# MotorDriver.net
KiCad netlist of a schematic drawn in Altium Designer
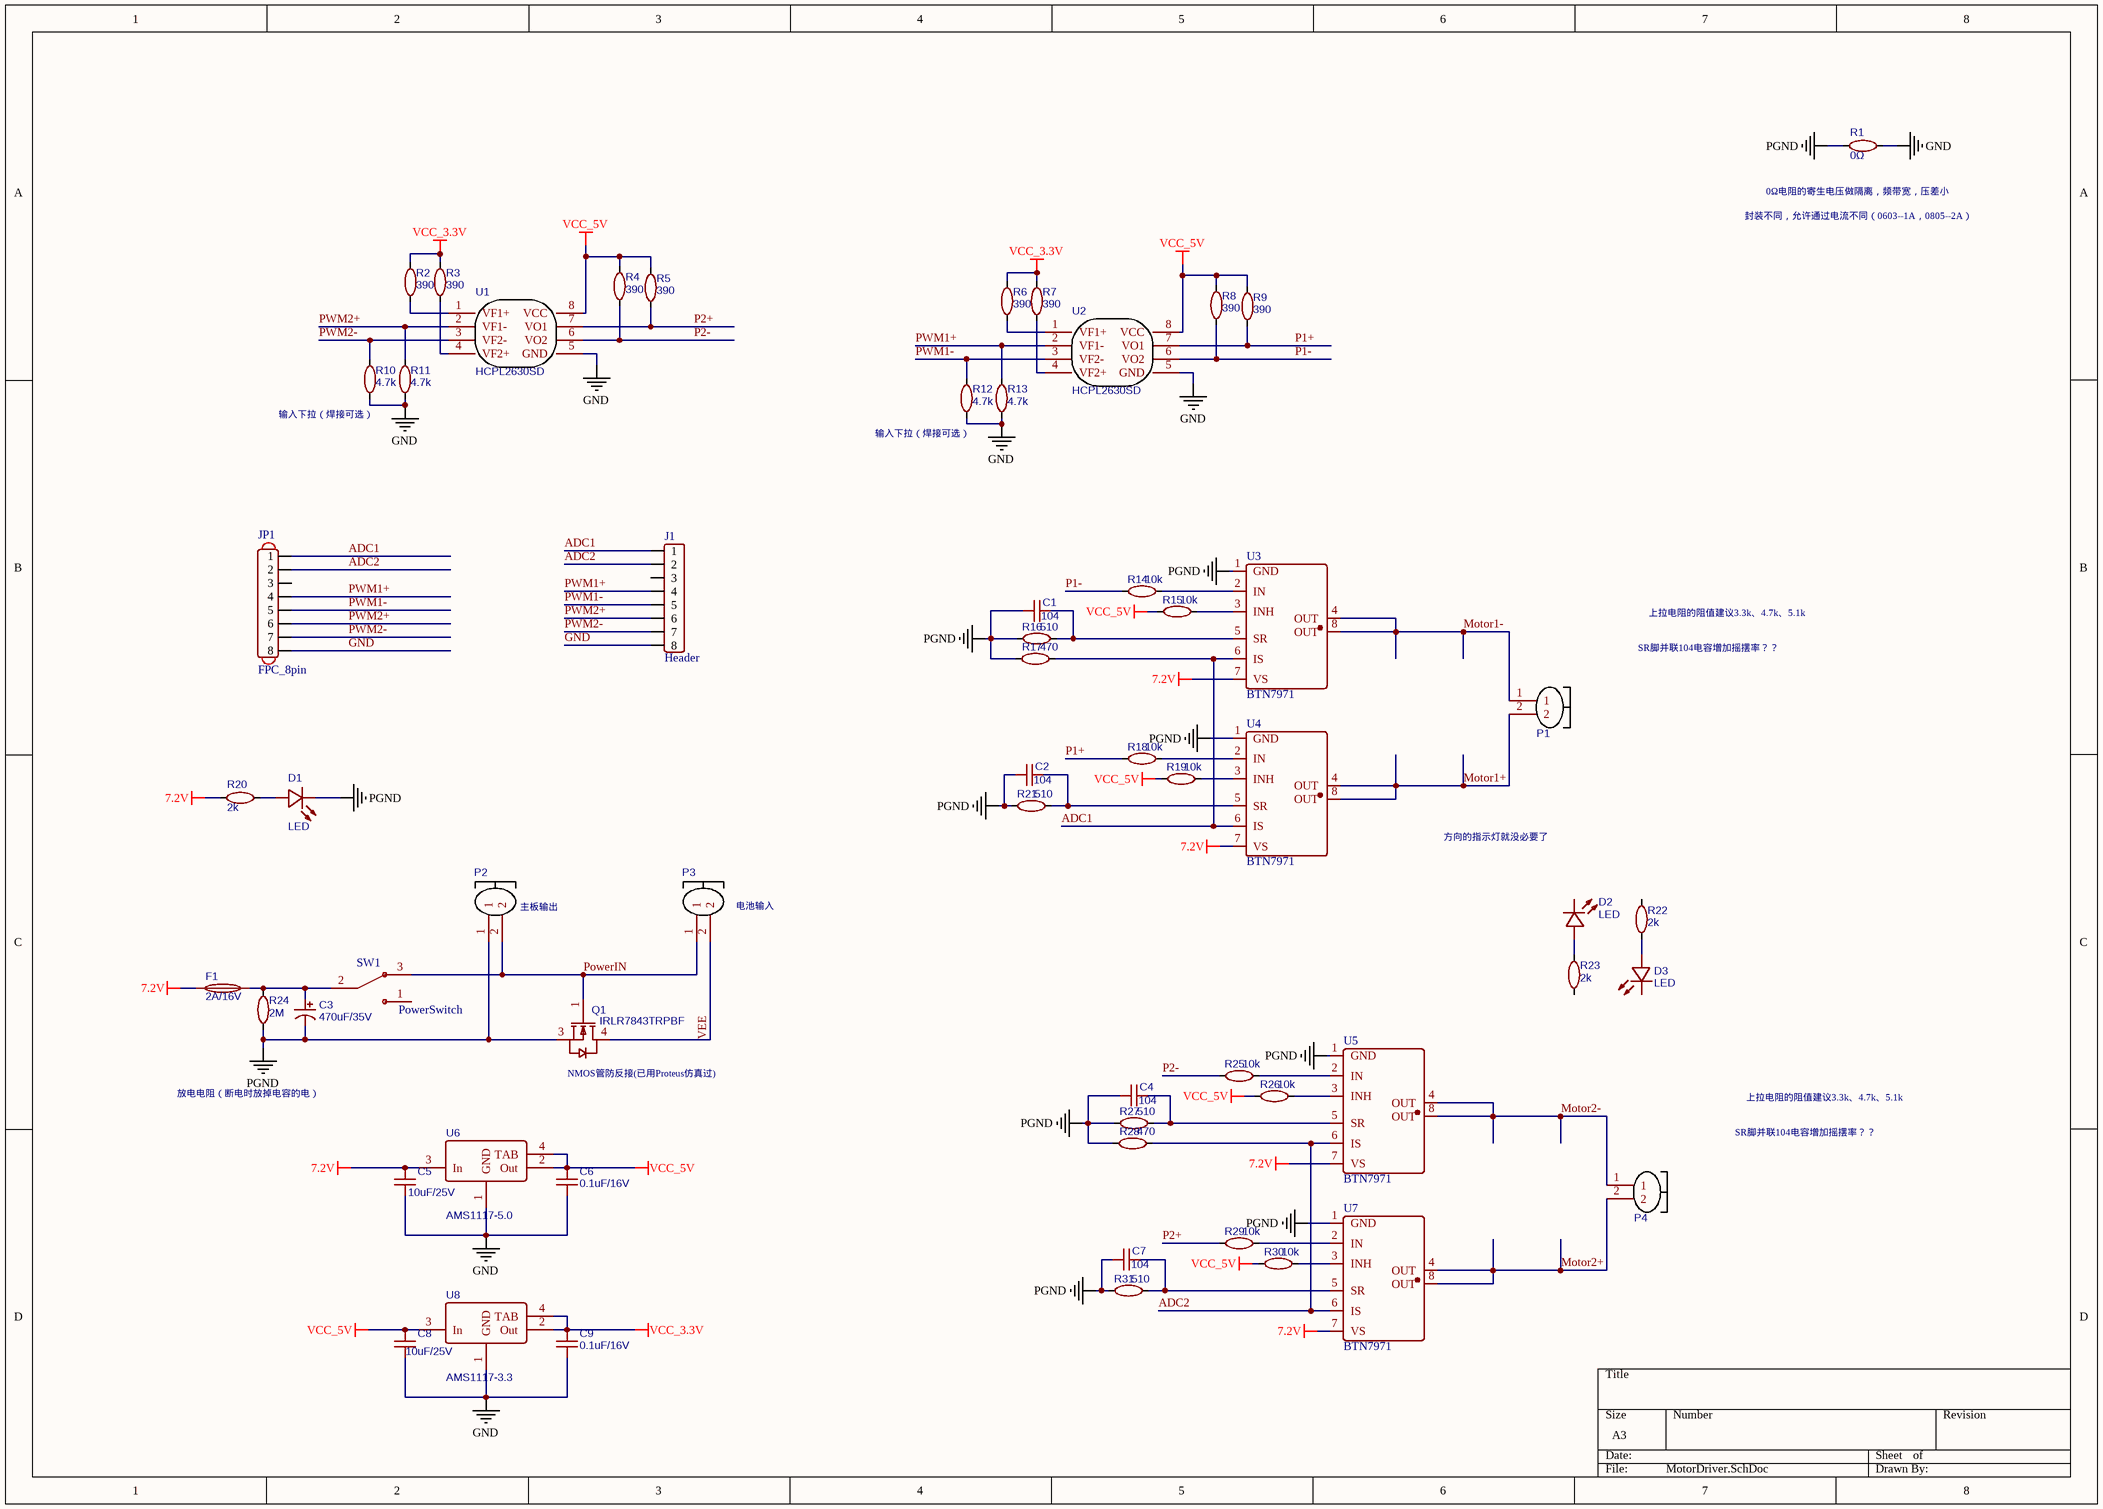
[diagram p0: MotorDriver.SchDoc]

(export (version "E")
  (design (tool "Eeschema 10.0.6"))
  (components
    (comp (ref "C1")
      (value "104")
      (footprint "CAP_0603")
      (fields
        (field (name "BOM_SUPPLIER PART") "C307348")
        (field (name "BOM_MANUFACTURER PART") "CL10B104KB8WPNC")
        (field (name "CONTRIBUTOR") "LCSC")
      )
      (libsource (lib "LTC_Library1") (part "CAP_0603"))
    )
    (comp (ref "C2")
      (value "104")
      (footprint "CAP_0603")
      (fields
        (field (name "BOM_SUPPLIER PART") "C307348")
        (field (name "BOM_MANUFACTURER PART") "CL10B104KB8WPNC")
        (field (name "CONTRIBUTOR") "LCSC")
      )
      (libsource (lib "LTC_Library1") (part "CAP_0603"))
    )
    (comp (ref "C3")
      (value "470uF/35V")
      (footprint "CAPE_TH_3.5_8")
      (description "直插电解电容")
      (fields
        (field (name "BOM_MANUFACTURER PART") "RVT1C221M0607")
        (field (name "BOM_SUPPLIER PART") "C72496")
      )
      (libsource (lib "LTC_Library1") (part "CAP_E_DIP"))
    )
    (comp (ref "C4")
      (value "104")
      (footprint "CAP_0603")
      (fields
        (field (name "BOM_SUPPLIER PART") "C307348")
        (field (name "BOM_MANUFACTURER PART") "CL10B104KB8WPNC")
        (field (name "CONTRIBUTOR") "LCSC")
      )
      (libsource (lib "LTC_Library1") (part "CAP_0603"))
    )
    (comp (ref "C5")
      (value "10uF/25V")
      (footprint "CAP_0603")
      (fields
        (field (name "BOM_SUPPLIER PART") "C307348")
        (field (name "BOM_MANUFACTURER PART") "CL10B104KB8WPNC")
        (field (name "CONTRIBUTOR") "LCSC")
      )
      (libsource (lib "LTC_Library1") (part "CAP_0603"))
    )
    (comp (ref "C6")
      (value "0.1uF/16V")
      (footprint "CAP_0603")
      (fields
        (field (name "BOM_SUPPLIER PART") "C307348")
        (field (name "BOM_MANUFACTURER PART") "CL10B104KB8WPNC")
        (field (name "CONTRIBUTOR") "LCSC")
      )
      (libsource (lib "LTC_Library1") (part "CAP_0603"))
    )
    (comp (ref "C7")
      (value "104")
      (footprint "CAP_0603")
      (fields
        (field (name "BOM_SUPPLIER PART") "C307348")
        (field (name "BOM_MANUFACTURER PART") "CL10B104KB8WPNC")
        (field (name "CONTRIBUTOR") "LCSC")
      )
      (libsource (lib "LTC_Library1") (part "CAP_0603"))
    )
    (comp (ref "C8")
      (value "10uF/25V")
      (footprint "CAP_0603")
      (fields
        (field (name "BOM_SUPPLIER PART") "C307348")
        (field (name "BOM_MANUFACTURER PART") "CL10B104KB8WPNC")
        (field (name "CONTRIBUTOR") "LCSC")
      )
      (libsource (lib "LTC_Library1") (part "CAP_0603"))
    )
    (comp (ref "C9")
      (value "0.1uF/16V")
      (footprint "CAP_0603")
      (fields
        (field (name "BOM_SUPPLIER PART") "C307348")
        (field (name "BOM_MANUFACTURER PART") "CL10B104KB8WPNC")
        (field (name "CONTRIBUTOR") "LCSC")
      )
      (libsource (lib "LTC_Library1") (part "CAP_0603"))
    )
    (comp (ref "D1")
      (value "LED")
      (footprint "LED_0603_B")
      (description "发光LED")
      (fields
        (field (name "BOM_MANUFACTURER PART") "D-G080508G1")
        (field (name "BOM_SUPPLIER PART") "C107402")
        (field (name "CONTRIBUTOR") "LCSC")
      )
      (libsource (lib "LTC_Library1") (part "LED_0603"))
    )
    (comp (ref "D2")
      (value "LED")
      (footprint "LED_0603_B")
      (description "发光LED")
      (fields
        (field (name "BOM_MANUFACTURER PART") "D-G080508G1")
        (field (name "BOM_SUPPLIER PART") "C107402")
        (field (name "CONTRIBUTOR") "LCSC")
      )
      (libsource (lib "LTC_Library1") (part "LED_0603"))
    )
    (comp (ref "D3")
      (value "LED")
      (footprint "LED_0603_B")
      (description "发光LED")
      (fields
        (field (name "BOM_MANUFACTURER PART") "D-G080508G1")
        (field (name "BOM_SUPPLIER PART") "C107402")
        (field (name "CONTRIBUTOR") "LCSC")
      )
      (libsource (lib "LTC_Library1") (part "LED_0603"))
    )
    (comp (ref "F1")
      (value "2A/16V")
      (footprint "F1206")
      (fields
        (field (name "BOM_SUPPLIER PART") "C369161")
        (field (name "BOM_MANUFACTURER PART") "JK-NSMD100-16V")
        (field (name "CONTRIBUTOR") "LCSC")
      )
      (libsource (lib "SmartCar_Library") (part "JK-NSMD100-16V"))
    )
    (comp (ref "J1")
      (value "Header")
      (footprint "Header 2.54X8")
      (libsource (lib "LTC_Library1") (part "Header 2.54_8"))
    )
    (comp (ref "JP1")
      (value "FPC_8pin")
      (footprint "FPC_1.0_8P")
      (libsource (lib "LTC_Library1") (part "FPC_8pin"))
    )
    (comp (ref "P1")
      (value "KF-2P-5.08")
      (footprint "KF_2P-5.08")
      (description "端子2P")
      (fields
        (field (name "BOM_MANUFACTURER PART") "WJ500H-5.08-2P")
        (field (name "BOM_SUPPLIER PART") "C8478")
      )
      (libsource (lib "LTC_Library1") (part "KF-2P-5.08"))
    )
    (comp (ref "P2")
      (value "KF-2P-5.08")
      (footprint "KF_2P-5.08")
      (description "端子2P")
      (fields
        (field (name "BOM_MANUFACTURER PART") "WJ500H-5.08-2P")
        (field (name "BOM_SUPPLIER PART") "C8478")
      )
      (libsource (lib "LTC_Library1") (part "KF-2P-5.08"))
    )
    (comp (ref "P3")
      (value "KF-2P-5.08")
      (footprint "KF_2P-5.08")
      (description "端子2P")
      (fields
        (field (name "BOM_MANUFACTURER PART") "WJ500H-5.08-2P")
        (field (name "BOM_SUPPLIER PART") "C8478")
      )
      (libsource (lib "LTC_Library1") (part "KF-2P-5.08"))
    )
    (comp (ref "P4")
      (value "KF-2P-5.08")
      (footprint "KF_2P-5.08")
      (description "端子2P")
      (fields
        (field (name "BOM_MANUFACTURER PART") "WJ500H-5.08-2P")
        (field (name "BOM_SUPPLIER PART") "C8478")
      )
      (libsource (lib "LTC_Library1") (part "KF-2P-5.08"))
    )
    (comp (ref "Q1")
      (value "IRLR7843TRPBF")
      (footprint "TO-252-2")
      (description "MOS管")
      (fields (field (name "BOM_SUPPLIER PART") "C21988"))
      (libsource (lib "LTC_Library1") (part "IRLR7843TRPBF"))
    )
    (comp (ref "R1")
      (value "0Ω")
      (footprint "RES_0805")
      (fields
        (field (name "BOM_MANUFACTURER PART") "RC0402JR-07100KL")
        (field (name "BOM_SUPPLIER PART") "C106234")
      )
      (libsource (lib "LTC_Library1") (part "RES_0805"))
    )
    (comp (ref "R2")
      (value "390")
      (footprint "RES_0603")
      (fields
        (field (name "BOM_MANUFACTURER PART") "RC0402JR-07100KL")
        (field (name "BOM_SUPPLIER PART") "C106234")
      )
      (libsource (lib "LTC_Library1") (part "RES_0603"))
    )
    (comp (ref "R3")
      (value "390")
      (footprint "RES_0603")
      (fields
        (field (name "BOM_MANUFACTURER PART") "RC0402JR-07100KL")
        (field (name "BOM_SUPPLIER PART") "C106234")
      )
      (libsource (lib "LTC_Library1") (part "RES_0603"))
    )
    (comp (ref "R4")
      (value "390")
      (footprint "RES_0603")
      (fields
        (field (name "BOM_MANUFACTURER PART") "RC0402JR-07100KL")
        (field (name "BOM_SUPPLIER PART") "C106234")
      )
      (libsource (lib "LTC_Library1") (part "RES_0603"))
    )
    (comp (ref "R5")
      (value "390")
      (footprint "RES_0603")
      (fields
        (field (name "BOM_MANUFACTURER PART") "RC0402JR-07100KL")
        (field (name "BOM_SUPPLIER PART") "C106234")
      )
      (libsource (lib "LTC_Library1") (part "RES_0603"))
    )
    (comp (ref "R6")
      (value "390")
      (footprint "RES_0603")
      (fields
        (field (name "BOM_MANUFACTURER PART") "RC0402JR-07100KL")
        (field (name "BOM_SUPPLIER PART") "C106234")
      )
      (libsource (lib "LTC_Library1") (part "RES_0603"))
    )
    (comp (ref "R7")
      (value "390")
      (footprint "RES_0603")
      (fields
        (field (name "BOM_MANUFACTURER PART") "RC0402JR-07100KL")
        (field (name "BOM_SUPPLIER PART") "C106234")
      )
      (libsource (lib "LTC_Library1") (part "RES_0603"))
    )
    (comp (ref "R8")
      (value "390")
      (footprint "RES_0603")
      (fields
        (field (name "BOM_MANUFACTURER PART") "RC0402JR-07100KL")
        (field (name "BOM_SUPPLIER PART") "C106234")
      )
      (libsource (lib "LTC_Library1") (part "RES_0603"))
    )
    (comp (ref "R9")
      (value "390")
      (footprint "RES_0603")
      (fields
        (field (name "BOM_MANUFACTURER PART") "RC0402JR-07100KL")
        (field (name "BOM_SUPPLIER PART") "C106234")
      )
      (libsource (lib "LTC_Library1") (part "RES_0603"))
    )
    (comp (ref "R10")
      (value "4.7k")
      (footprint "RES_0603")
      (fields
        (field (name "BOM_MANUFACTURER PART") "RC0402JR-07100KL")
        (field (name "BOM_SUPPLIER PART") "C106234")
      )
      (libsource (lib "LTC_Library1") (part "RES_0603"))
    )
    (comp (ref "R11")
      (value "4.7k")
      (footprint "RES_0603")
      (fields
        (field (name "BOM_MANUFACTURER PART") "RC0402JR-07100KL")
        (field (name "BOM_SUPPLIER PART") "C106234")
      )
      (libsource (lib "LTC_Library1") (part "RES_0603"))
    )
    (comp (ref "R12")
      (value "4.7k")
      (footprint "RES_0603")
      (fields
        (field (name "BOM_MANUFACTURER PART") "RC0402JR-07100KL")
        (field (name "BOM_SUPPLIER PART") "C106234")
      )
      (libsource (lib "LTC_Library1") (part "RES_0603"))
    )
    (comp (ref "R13")
      (value "4.7k")
      (footprint "RES_0603")
      (fields
        (field (name "BOM_MANUFACTURER PART") "RC0402JR-07100KL")
        (field (name "BOM_SUPPLIER PART") "C106234")
      )
      (libsource (lib "LTC_Library1") (part "RES_0603"))
    )
    (comp (ref "R14")
      (value "10k")
      (footprint "RES_0603")
      (fields
        (field (name "BOM_MANUFACTURER PART") "RC0402JR-07100KL")
        (field (name "BOM_SUPPLIER PART") "C106234")
      )
      (libsource (lib "LTC_Library1") (part "RES_0603"))
    )
    (comp (ref "R15")
      (value "10k")
      (footprint "RES_0603")
      (fields
        (field (name "BOM_MANUFACTURER PART") "RC0402JR-07100KL")
        (field (name "BOM_SUPPLIER PART") "C106234")
      )
      (libsource (lib "LTC_Library1") (part "RES_0603"))
    )
    (comp (ref "R16")
      (value "510")
      (footprint "RES_0603")
      (fields
        (field (name "BOM_MANUFACTURER PART") "RC0402JR-07100KL")
        (field (name "BOM_SUPPLIER PART") "C106234")
      )
      (libsource (lib "LTC_Library1") (part "RES_0603"))
    )
    (comp (ref "R17")
      (value "470")
      (footprint "RES_0603")
      (fields
        (field (name "BOM_MANUFACTURER PART") "RC0402JR-07100KL")
        (field (name "BOM_SUPPLIER PART") "C106234")
      )
      (libsource (lib "LTC_Library1") (part "RES_0603"))
    )
    (comp (ref "R18")
      (value "10k")
      (footprint "RES_0603")
      (fields
        (field (name "BOM_MANUFACTURER PART") "RC0402JR-07100KL")
        (field (name "BOM_SUPPLIER PART") "C106234")
      )
      (libsource (lib "LTC_Library1") (part "RES_0603"))
    )
    (comp (ref "R19")
      (value "10k")
      (footprint "RES_0603")
      (fields
        (field (name "BOM_MANUFACTURER PART") "RC0402JR-07100KL")
        (field (name "BOM_SUPPLIER PART") "C106234")
      )
      (libsource (lib "LTC_Library1") (part "RES_0603"))
    )
    (comp (ref "R20")
      (value "2k")
      (footprint "RES_0603")
      (fields
        (field (name "BOM_MANUFACTURER PART") "RC0402JR-07100KL")
        (field (name "BOM_SUPPLIER PART") "C106234")
      )
      (libsource (lib "LTC_Library1") (part "RES_0603"))
    )
    (comp (ref "R21")
      (value "510")
      (footprint "RES_0603")
      (fields
        (field (name "BOM_MANUFACTURER PART") "RC0402JR-07100KL")
        (field (name "BOM_SUPPLIER PART") "C106234")
      )
      (libsource (lib "LTC_Library1") (part "RES_0603"))
    )
    (comp (ref "R22")
      (value "2k")
      (footprint "RES_0603")
      (fields
        (field (name "BOM_MANUFACTURER PART") "RC0402JR-07100KL")
        (field (name "BOM_SUPPLIER PART") "C106234")
      )
      (libsource (lib "LTC_Library1") (part "RES_0603"))
    )
    (comp (ref "R23")
      (value "2k")
      (footprint "RES_0603")
      (fields
        (field (name "BOM_MANUFACTURER PART") "RC0402JR-07100KL")
        (field (name "BOM_SUPPLIER PART") "C106234")
      )
      (libsource (lib "LTC_Library1") (part "RES_0603"))
    )
    (comp (ref "R24")
      (value "2M")
      (footprint "RES_0805")
      (fields
        (field (name "BOM_MANUFACTURER PART") "RC0402JR-07100KL")
        (field (name "BOM_SUPPLIER PART") "C106234")
      )
      (libsource (lib "LTC_Library1") (part "RES_0805"))
    )
    (comp (ref "R25")
      (value "10k")
      (footprint "RES_0603")
      (fields
        (field (name "BOM_MANUFACTURER PART") "RC0402JR-07100KL")
        (field (name "BOM_SUPPLIER PART") "C106234")
      )
      (libsource (lib "LTC_Library1") (part "RES_0603"))
    )
    (comp (ref "R26")
      (value "10k")
      (footprint "RES_0603")
      (fields
        (field (name "BOM_MANUFACTURER PART") "RC0402JR-07100KL")
        (field (name "BOM_SUPPLIER PART") "C106234")
      )
      (libsource (lib "LTC_Library1") (part "RES_0603"))
    )
    (comp (ref "R27")
      (value "510")
      (footprint "RES_0603")
      (fields
        (field (name "BOM_MANUFACTURER PART") "RC0402JR-07100KL")
        (field (name "BOM_SUPPLIER PART") "C106234")
      )
      (libsource (lib "LTC_Library1") (part "RES_0603"))
    )
    (comp (ref "R28")
      (value "470")
      (footprint "RES_0603")
      (fields
        (field (name "BOM_MANUFACTURER PART") "RC0402JR-07100KL")
        (field (name "BOM_SUPPLIER PART") "C106234")
      )
      (libsource (lib "LTC_Library1") (part "RES_0603"))
    )
    (comp (ref "R29")
      (value "10k")
      (footprint "RES_0603")
      (fields
        (field (name "BOM_MANUFACTURER PART") "RC0402JR-07100KL")
        (field (name "BOM_SUPPLIER PART") "C106234")
      )
      (libsource (lib "LTC_Library1") (part "RES_0603"))
    )
    (comp (ref "R30")
      (value "10k")
      (footprint "RES_0603")
      (fields
        (field (name "BOM_MANUFACTURER PART") "RC0402JR-07100KL")
        (field (name "BOM_SUPPLIER PART") "C106234")
      )
      (libsource (lib "LTC_Library1") (part "RES_0603"))
    )
    (comp (ref "R31")
      (value "510")
      (footprint "RES_0603")
      (fields
        (field (name "BOM_MANUFACTURER PART") "RC0402JR-07100KL")
        (field (name "BOM_SUPPLIER PART") "C106234")
      )
      (libsource (lib "LTC_Library1") (part "RES_0603"))
    )
    (comp (ref "SW1")
      (value "PowerSwitch")
      (footprint "SW-TH_K3-1260D-K1")
      (libsource (lib "SmartCar_Library") (part "PowerSwitch"))
    )
    (comp (ref "U1")
      (value "HCPL2630SD")
      (footprint "SOP8_2_54")
      (fields (field (name "BOM_SUPPLIER PART") "C46037"))
      (libsource (lib "LTC_Library1") (part "HCPL2630SD"))
    )
    (comp (ref "U2")
      (value "HCPL2630SD")
      (footprint "SOP8_2_54")
      (fields (field (name "BOM_SUPPLIER PART") "C46037"))
      (libsource (lib "LTC_Library1") (part "HCPL2630SD"))
    )
    (comp (ref "U3")
      (value "BTN7971")
      (footprint "TO263_7")
      (libsource (lib "LTC_Library1") (part "BTN7971"))
    )
    (comp (ref "U4")
      (value "BTN7971")
      (footprint "TO263_7")
      (libsource (lib "LTC_Library1") (part "BTN7971"))
    )
    (comp (ref "U5")
      (value "BTN7971")
      (footprint "TO263_7")
      (libsource (lib "LTC_Library1") (part "BTN7971"))
    )
    (comp (ref "U6")
      (value "AMS1117-5.0")
      (footprint "SOT-223_3")
      (fields
        (field (name "BOM_SUPPLIER PART") "C165482")
        (field (name "BOM_MANUFACTURER PART") "AMS1117-3.3")
        (field (name "CONTRIBUTOR") "LCSC")
      )
      (libsource (lib "LTC_Library1") (part "AMS1117-5.0"))
    )
    (comp (ref "U7")
      (value "BTN7971")
      (footprint "TO263_7")
      (libsource (lib "LTC_Library1") (part "BTN7971"))
    )
    (comp (ref "U8")
      (value "AMS1117-3.3")
      (footprint "SOT-223_3")
      (fields (field (name "BOM_SUPPLIER PART") "C165482") (field (name "CONTRIBUTOR") "LCSC"))
      (libsource (lib "LTC_Library1") (part "AMS1117-3.3"))
    )
  )
  (nets
    (net (code "1") (name "/ADC1") (class "Default")
      (node (ref "J1") (pin "1") (pinfunction "1_1") (pintype "passive"))
      (node (ref "JP1") (pin "1") (pinfunction "1_1") (pintype "passive"))
      (node (ref "R17") (pin "2") (pinfunction "2_2") (pintype "passive"))
      (node (ref "U3") (pin "6") (pinfunction "IS_6") (pintype "passive"))
      (node (ref "U4") (pin "6") (pinfunction "IS_6") (pintype "passive"))
    )
    (net (code "2") (name "/ADC2") (class "Default")
      (node (ref "J1") (pin "2") (pinfunction "2_2") (pintype "passive"))
      (node (ref "JP1") (pin "2") (pinfunction "2_2") (pintype "passive"))
      (node (ref "R28") (pin "2") (pinfunction "2_2") (pintype "passive"))
      (node (ref "U5") (pin "6") (pinfunction "IS_6") (pintype "passive"))
      (node (ref "U7") (pin "6") (pinfunction "IS_6") (pintype "passive"))
    )
    (net (code "3") (name "/Motor1+") (class "Default")
      (node (ref "P1") (pin "2") (pinfunction "2_2") (pintype "passive"))
      (node (ref "U4") (pin "4") (pinfunction "OUT_4") (pintype "passive"))
      (node (ref "U4") (pin "8") (pinfunction "OUT_8") (pintype "passive"))
    )
    (net (code "4") (name "/Motor1-") (class "Default")
      (node (ref "P1") (pin "1") (pinfunction "1_1") (pintype "passive"))
      (node (ref "U3") (pin "4") (pinfunction "OUT_4") (pintype "passive"))
      (node (ref "U3") (pin "8") (pinfunction "OUT_8") (pintype "passive"))
    )
    (net (code "5") (name "/Motor2+") (class "Default")
      (node (ref "P4") (pin "2") (pinfunction "2_2") (pintype "passive"))
      (node (ref "U7") (pin "4") (pinfunction "OUT_4") (pintype "passive"))
      (node (ref "U7") (pin "8") (pinfunction "OUT_8") (pintype "passive"))
    )
    (net (code "6") (name "/Motor2-") (class "Default")
      (node (ref "P4") (pin "1") (pinfunction "1_1") (pintype "passive"))
      (node (ref "U5") (pin "4") (pinfunction "OUT_4") (pintype "passive"))
      (node (ref "U5") (pin "8") (pinfunction "OUT_8") (pintype "passive"))
    )
    (net (code "7") (name "/P1+") (class "Default")
      (node (ref "R18") (pin "2") (pinfunction "2_2") (pintype "passive"))
      (node (ref "R9") (pin "1") (pinfunction "1_1") (pintype "passive"))
      (node (ref "U2") (pin "7") (pinfunction "VO1_7") (pintype "passive"))
    )
    (net (code "8") (name "/P1-") (class "Default")
      (node (ref "R14") (pin "2") (pinfunction "2_2") (pintype "passive"))
      (node (ref "R8") (pin "1") (pinfunction "1_1") (pintype "passive"))
      (node (ref "U2") (pin "6") (pinfunction "VO2_6") (pintype "passive"))
    )
    (net (code "9") (name "/P2+") (class "Default")
      (node (ref "R29") (pin "2") (pinfunction "2_2") (pintype "passive"))
      (node (ref "R5") (pin "1") (pinfunction "1_1") (pintype "passive"))
      (node (ref "U1") (pin "7") (pinfunction "VO1_7") (pintype "passive"))
    )
    (net (code "10") (name "/P2-") (class "Default")
      (node (ref "R25") (pin "2") (pinfunction "2_2") (pintype "passive"))
      (node (ref "R4") (pin "1") (pinfunction "1_1") (pintype "passive"))
      (node (ref "U1") (pin "6") (pinfunction "VO2_6") (pintype "passive"))
    )
    (net (code "11") (name "/PWM1+") (class "Default")
      (node (ref "J1") (pin "4") (pinfunction "4_4") (pintype "passive"))
      (node (ref "JP1") (pin "4") (pinfunction "4_4") (pintype "passive"))
      (node (ref "R13") (pin "2") (pinfunction "2_2") (pintype "passive"))
      (node (ref "U2") (pin "2") (pinfunction "VF1-_2") (pintype "passive"))
    )
    (net (code "12") (name "/PWM1-") (class "Default")
      (node (ref "J1") (pin "5") (pinfunction "5_5") (pintype "passive"))
      (node (ref "JP1") (pin "5") (pinfunction "5_5") (pintype "passive"))
      (node (ref "R12") (pin "2") (pinfunction "2_2") (pintype "passive"))
      (node (ref "U2") (pin "3") (pinfunction "VF2-_3") (pintype "passive"))
    )
    (net (code "13") (name "/PWM2+") (class "Default")
      (node (ref "J1") (pin "6") (pinfunction "6_6") (pintype "passive"))
      (node (ref "JP1") (pin "6") (pinfunction "6_6") (pintype "passive"))
      (node (ref "R11") (pin "2") (pinfunction "2_2") (pintype "passive"))
      (node (ref "U1") (pin "2") (pinfunction "VF1-_2") (pintype "passive"))
    )
    (net (code "14") (name "/PWM2-") (class "Default")
      (node (ref "J1") (pin "7") (pinfunction "7_7") (pintype "passive"))
      (node (ref "JP1") (pin "7") (pinfunction "7_7") (pintype "passive"))
      (node (ref "R10") (pin "2") (pinfunction "2_2") (pintype "passive"))
      (node (ref "U1") (pin "3") (pinfunction "VF2-_3") (pintype "passive"))
    )
    (net (code "15") (name "/PowerIN") (class "Default")
      (node (ref "P2") (pin "2") (pinfunction "2_2") (pintype "passive"))
      (node (ref "P3") (pin "1") (pinfunction "1_1") (pintype "passive"))
      (node (ref "Q1") (pin "1") (pinfunction "G_1") (pintype "passive"))
      (node (ref "SW1") (pin "3") (pinfunction "NC_3") (pintype "passive"))
    )
    (net (code "16") (name "/VEE") (class "Default")
      (node (ref "P3") (pin "2") (pinfunction "2_2") (pintype "passive"))
      (node (ref "Q1") (pin "4") (pinfunction "D_4") (pintype "passive"))
    )
    (net (code "17") (name "7.2V") (class "Default")
      (node (ref "C5") (pin "1") (pinfunction "1_1") (pintype "passive"))
      (node (ref "F1") (pin "1") (pinfunction "1_1") (pintype "passive"))
      (node (ref "R20") (pin "1") (pinfunction "1_1") (pintype "passive"))
      (node (ref "U3") (pin "7") (pinfunction "VS_7") (pintype "passive"))
      (node (ref "U4") (pin "7") (pinfunction "VS_7") (pintype "passive"))
      (node (ref "U5") (pin "7") (pinfunction "VS_7") (pintype "passive"))
      (node (ref "U6") (pin "3") (pinfunction "In_3") (pintype "passive"))
      (node (ref "U7") (pin "7") (pinfunction "VS_7") (pintype "passive"))
    )
    (net (code "18") (name "GND") (class "Default")
      (node (ref "C5") (pin "2") (pinfunction "2_2") (pintype "passive"))
      (node (ref "C6") (pin "2") (pinfunction "2_2") (pintype "passive"))
      (node (ref "C8") (pin "2") (pinfunction "2_2") (pintype "passive"))
      (node (ref "C9") (pin "2") (pinfunction "2_2") (pintype "passive"))
      (node (ref "J1") (pin "8") (pinfunction "8_8") (pintype "passive"))
      (node (ref "JP1") (pin "8") (pinfunction "8_8") (pintype "passive"))
      (node (ref "R1") (pin "1") (pinfunction "1_1") (pintype "passive"))
      (node (ref "R10") (pin "1") (pinfunction "1_1") (pintype "passive"))
      (node (ref "R11") (pin "1") (pinfunction "1_1") (pintype "passive"))
      (node (ref "R12") (pin "1") (pinfunction "1_1") (pintype "passive"))
      (node (ref "R13") (pin "1") (pinfunction "1_1") (pintype "passive"))
      (node (ref "U1") (pin "5") (pinfunction "GND_5") (pintype "passive"))
      (node (ref "U2") (pin "5") (pinfunction "GND_5") (pintype "passive"))
      (node (ref "U6") (pin "1") (pinfunction "GND_1") (pintype "passive"))
      (node (ref "U8") (pin "1") (pinfunction "GND_1") (pintype "passive"))
    )
    (net (code "19") (name "Net-(D1-PadA)") (class "Default")
      (node (ref "D1") (pin "A") (pinfunction "A_A") (pintype "passive"))
      (node (ref "R20") (pin "2") (pinfunction "2_2") (pintype "passive"))
    )
    (net (code "20") (name "Net-(D2-PadA)") (class "Default")
      (node (ref "D2") (pin "A") (pinfunction "A_A") (pintype "passive"))
      (node (ref "R23") (pin "2") (pinfunction "2_2") (pintype "passive"))
    )
    (net (code "21") (name "Net-(D3-PadA)") (class "Default")
      (node (ref "D3") (pin "A") (pinfunction "A_A") (pintype "passive"))
      (node (ref "R22") (pin "2") (pinfunction "2_2") (pintype "passive"))
    )
    (net (code "22") (name "Net-(SW1-C)") (class "Default")
      (node (ref "C3") (pin "1") (pinfunction "1_1") (pintype "passive"))
      (node (ref "F1") (pin "2") (pinfunction "2_2") (pintype "passive"))
      (node (ref "R24") (pin "2") (pinfunction "2_2") (pintype "passive"))
      (node (ref "SW1") (pin "2") (pinfunction "C_2") (pintype "passive"))
    )
    (net (code "23") (name "Net-(U1-VF1+)") (class "Default")
      (node (ref "R2") (pin "1") (pinfunction "1_1") (pintype "passive"))
      (node (ref "U1") (pin "1") (pinfunction "VF1+_1") (pintype "passive"))
    )
    (net (code "24") (name "Net-(U1-VF2+)") (class "Default")
      (node (ref "R3") (pin "1") (pinfunction "1_1") (pintype "passive"))
      (node (ref "U1") (pin "4") (pinfunction "VF2+_4") (pintype "passive"))
    )
    (net (code "25") (name "Net-(U2-VF1+)") (class "Default")
      (node (ref "R6") (pin "1") (pinfunction "1_1") (pintype "passive"))
      (node (ref "U2") (pin "1") (pinfunction "VF1+_1") (pintype "passive"))
    )
    (net (code "26") (name "Net-(U2-VF2+)") (class "Default")
      (node (ref "R7") (pin "1") (pinfunction "1_1") (pintype "passive"))
      (node (ref "U2") (pin "4") (pinfunction "VF2+_4") (pintype "passive"))
    )
    (net (code "27") (name "Net-(U3-IN)") (class "Default")
      (node (ref "R14") (pin "1") (pinfunction "1_1") (pintype "passive"))
      (node (ref "U3") (pin "2") (pinfunction "IN_2") (pintype "passive"))
    )
    (net (code "28") (name "Net-(U3-INH)") (class "Default")
      (node (ref "R15") (pin "1") (pinfunction "1_1") (pintype "passive"))
      (node (ref "U3") (pin "3") (pinfunction "INH_3") (pintype "passive"))
    )
    (net (code "29") (name "Net-(U3-SR)") (class "Default")
      (node (ref "C1") (pin "2") (pinfunction "2_2") (pintype "passive"))
      (node (ref "R16") (pin "1") (pinfunction "1_1") (pintype "passive"))
      (node (ref "U3") (pin "5") (pinfunction "SR_5") (pintype "passive"))
    )
    (net (code "30") (name "Net-(U4-IN)") (class "Default")
      (node (ref "R18") (pin "1") (pinfunction "1_1") (pintype "passive"))
      (node (ref "U4") (pin "2") (pinfunction "IN_2") (pintype "passive"))
    )
    (net (code "31") (name "Net-(U4-INH)") (class "Default")
      (node (ref "R19") (pin "1") (pinfunction "1_1") (pintype "passive"))
      (node (ref "U4") (pin "3") (pinfunction "INH_3") (pintype "passive"))
    )
    (net (code "32") (name "Net-(U4-SR)") (class "Default")
      (node (ref "C2") (pin "2") (pinfunction "2_2") (pintype "passive"))
      (node (ref "R21") (pin "1") (pinfunction "1_1") (pintype "passive"))
      (node (ref "U4") (pin "5") (pinfunction "SR_5") (pintype "passive"))
    )
    (net (code "33") (name "Net-(U5-IN)") (class "Default")
      (node (ref "R25") (pin "1") (pinfunction "1_1") (pintype "passive"))
      (node (ref "U5") (pin "2") (pinfunction "IN_2") (pintype "passive"))
    )
    (net (code "34") (name "Net-(U5-INH)") (class "Default")
      (node (ref "R26") (pin "1") (pinfunction "1_1") (pintype "passive"))
      (node (ref "U5") (pin "3") (pinfunction "INH_3") (pintype "passive"))
    )
    (net (code "35") (name "Net-(U5-SR)") (class "Default")
      (node (ref "C4") (pin "2") (pinfunction "2_2") (pintype "passive"))
      (node (ref "R27") (pin "1") (pinfunction "1_1") (pintype "passive"))
      (node (ref "U5") (pin "5") (pinfunction "SR_5") (pintype "passive"))
    )
    (net (code "36") (name "Net-(U7-IN)") (class "Default")
      (node (ref "R29") (pin "1") (pinfunction "1_1") (pintype "passive"))
      (node (ref "U7") (pin "2") (pinfunction "IN_2") (pintype "passive"))
    )
    (net (code "37") (name "Net-(U7-INH)") (class "Default")
      (node (ref "R30") (pin "1") (pinfunction "1_1") (pintype "passive"))
      (node (ref "U7") (pin "3") (pinfunction "INH_3") (pintype "passive"))
    )
    (net (code "38") (name "Net-(U7-SR)") (class "Default")
      (node (ref "C7") (pin "2") (pinfunction "2_2") (pintype "passive"))
      (node (ref "R31") (pin "1") (pinfunction "1_1") (pintype "passive"))
      (node (ref "U7") (pin "5") (pinfunction "SR_5") (pintype "passive"))
    )
    (net (code "39") (name "PGND") (class "Default")
      (node (ref "C1") (pin "1") (pinfunction "1_1") (pintype "passive"))
      (node (ref "C2") (pin "1") (pinfunction "1_1") (pintype "passive"))
      (node (ref "C3") (pin "2") (pinfunction "2_2") (pintype "passive"))
      (node (ref "C4") (pin "1") (pinfunction "1_1") (pintype "passive"))
      (node (ref "C7") (pin "1") (pinfunction "1_1") (pintype "passive"))
      (node (ref "D1") (pin "C") (pinfunction "C_C") (pintype "passive"))
      (node (ref "P2") (pin "1") (pinfunction "1_1") (pintype "passive"))
      (node (ref "Q1") (pin "3") (pinfunction "S_3") (pintype "passive"))
      (node (ref "R1") (pin "2") (pinfunction "2_2") (pintype "passive"))
      (node (ref "R16") (pin "2") (pinfunction "2_2") (pintype "passive"))
      (node (ref "R17") (pin "1") (pinfunction "1_1") (pintype "passive"))
      (node (ref "R21") (pin "2") (pinfunction "2_2") (pintype "passive"))
      (node (ref "R24") (pin "1") (pinfunction "1_1") (pintype "passive"))
      (node (ref "R27") (pin "2") (pinfunction "2_2") (pintype "passive"))
      (node (ref "R28") (pin "1") (pinfunction "1_1") (pintype "passive"))
      (node (ref "R31") (pin "2") (pinfunction "2_2") (pintype "passive"))
      (node (ref "U3") (pin "1") (pinfunction "GND_1") (pintype "passive"))
      (node (ref "U4") (pin "1") (pinfunction "GND_1") (pintype "passive"))
      (node (ref "U5") (pin "1") (pinfunction "GND_1") (pintype "passive"))
      (node (ref "U7") (pin "1") (pinfunction "GND_1") (pintype "passive"))
    )
    (net (code "40") (name "VCC_3.3V") (class "Default")
      (node (ref "C9") (pin "1") (pinfunction "1_1") (pintype "passive"))
      (node (ref "R2") (pin "2") (pinfunction "2_2") (pintype "passive"))
      (node (ref "R3") (pin "2") (pinfunction "2_2") (pintype "passive"))
      (node (ref "R6") (pin "2") (pinfunction "2_2") (pintype "passive"))
      (node (ref "R7") (pin "2") (pinfunction "2_2") (pintype "passive"))
      (node (ref "U8") (pin "2") (pinfunction "Out_2") (pintype "passive"))
      (node (ref "U8") (pin "4") (pinfunction "TAB_4") (pintype "passive"))
    )
    (net (code "41") (name "VCC_5V") (class "Default")
      (node (ref "C6") (pin "1") (pinfunction "1_1") (pintype "passive"))
      (node (ref "C8") (pin "1") (pinfunction "1_1") (pintype "passive"))
      (node (ref "R15") (pin "2") (pinfunction "2_2") (pintype "passive"))
      (node (ref "R19") (pin "2") (pinfunction "2_2") (pintype "passive"))
      (node (ref "R26") (pin "2") (pinfunction "2_2") (pintype "passive"))
      (node (ref "R30") (pin "2") (pinfunction "2_2") (pintype "passive"))
      (node (ref "R4") (pin "2") (pinfunction "2_2") (pintype "passive"))
      (node (ref "R5") (pin "2") (pinfunction "2_2") (pintype "passive"))
      (node (ref "R8") (pin "2") (pinfunction "2_2") (pintype "passive"))
      (node (ref "R9") (pin "2") (pinfunction "2_2") (pintype "passive"))
      (node (ref "U1") (pin "8") (pinfunction "VCC_8") (pintype "passive"))
      (node (ref "U2") (pin "8") (pinfunction "VCC_8") (pintype "passive"))
      (node (ref "U6") (pin "2") (pinfunction "Out_2") (pintype "passive"))
      (node (ref "U6") (pin "4") (pinfunction "TAB_4") (pintype "passive"))
      (node (ref "U8") (pin "3") (pinfunction "In_3") (pintype "passive"))
    )
    (net (code "42") (name "unconnected-(D2-PadC)") (class "Default")
      (node (ref "D2") (pin "C") (pinfunction "C_C") (pintype "passive"))
    )
    (net (code "43") (name "unconnected-(D3-PadC)") (class "Default")
      (node (ref "D3") (pin "C") (pinfunction "C_C") (pintype "passive"))
    )
    (net (code "44") (name "unconnected-(J1-Pad3)") (class "Default")
      (node (ref "J1") (pin "3") (pinfunction "3_3") (pintype "passive"))
    )
    (net (code "45") (name "unconnected-(JP1-Pad3)") (class "Default")
      (node (ref "JP1") (pin "3") (pinfunction "3_3") (pintype "passive"))
    )
    (net (code "46") (name "unconnected-(R22-Pad1)") (class "Default")
      (node (ref "R22") (pin "1") (pinfunction "1_1") (pintype "passive"))
    )
    (net (code "47") (name "unconnected-(R23-Pad1)") (class "Default")
      (node (ref "R23") (pin "1") (pinfunction "1_1") (pintype "passive"))
    )
    (net (code "48") (name "unconnected-(SW1-ON-Pad1)") (class "Default")
      (node (ref "SW1") (pin "1") (pinfunction "ON_1") (pintype "passive"))
    )
  )
)
